# FRONT_MCU_v1.net
KiCad netlist of a schematic drawn in Altium Designer
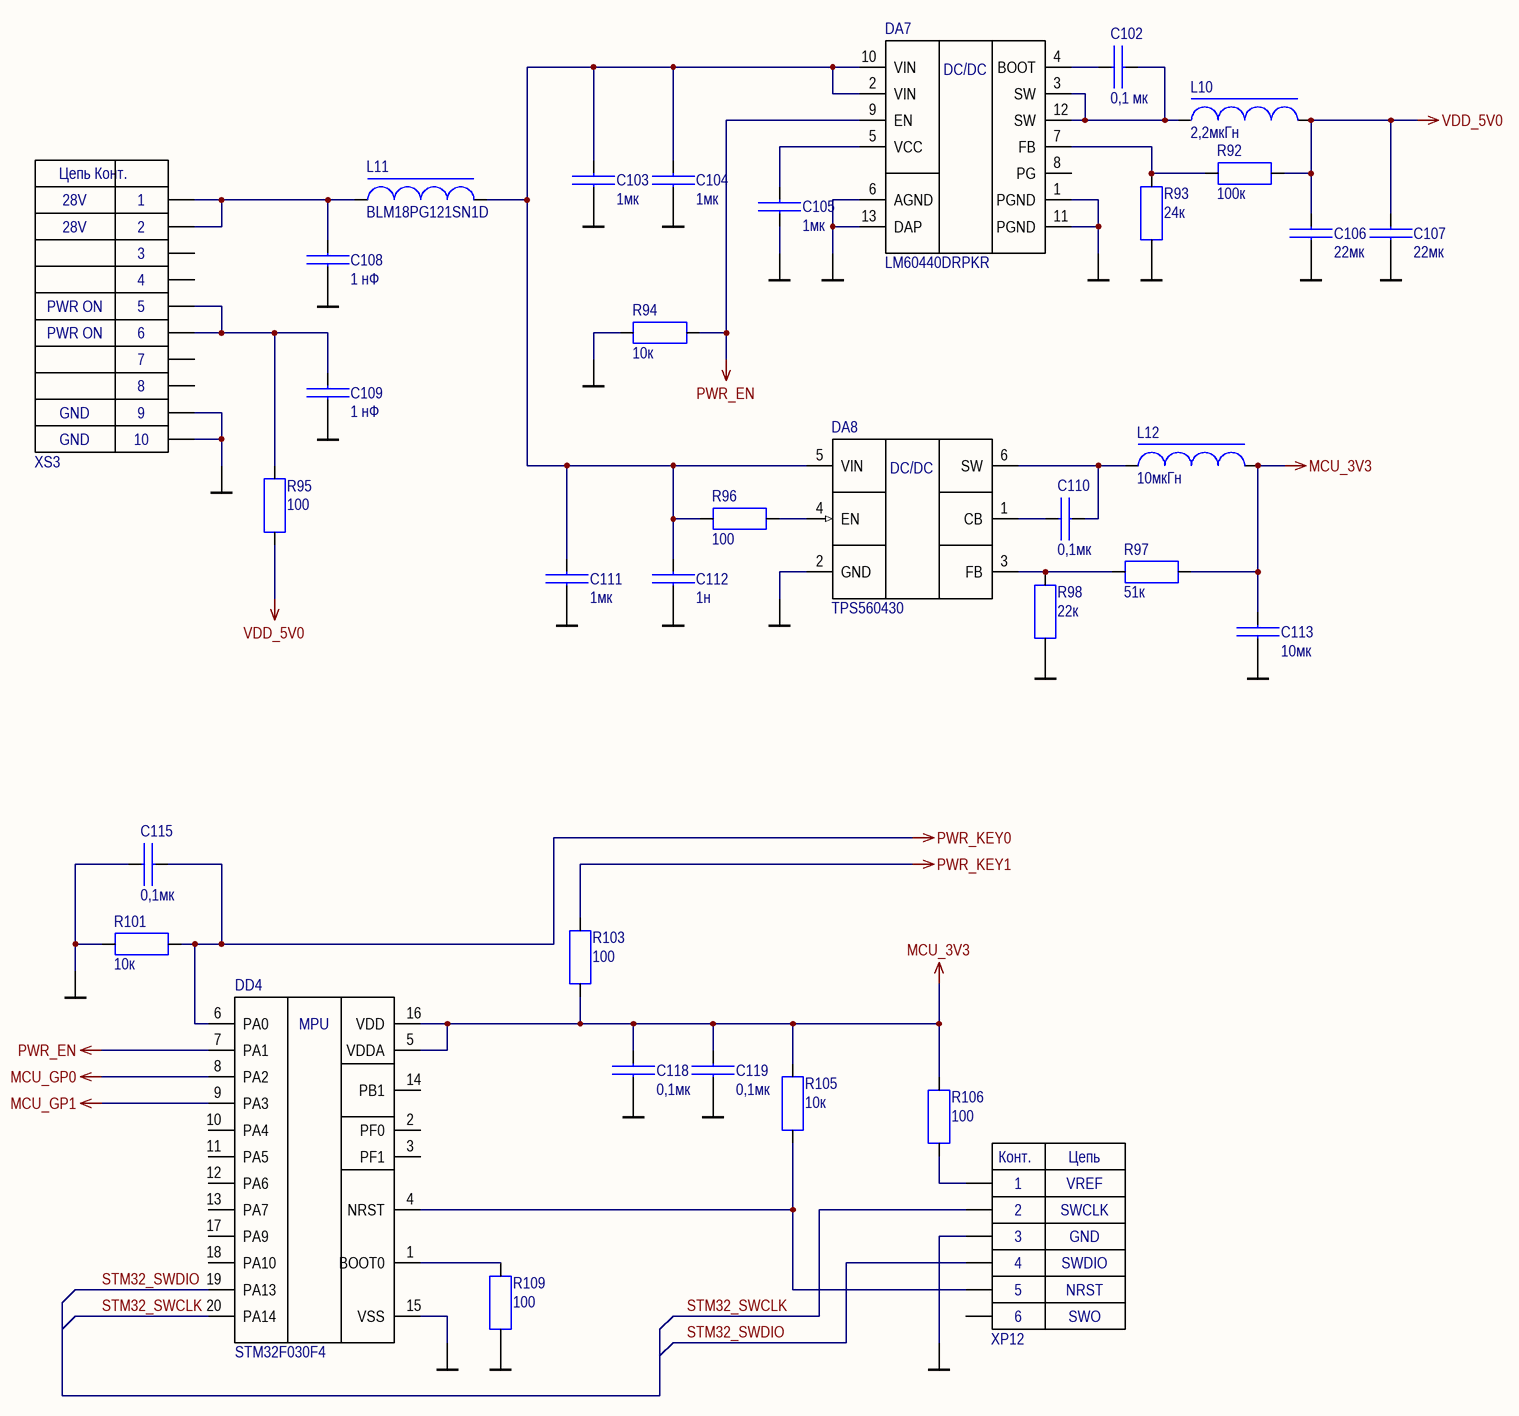
[diagram p0: FRONT_MCU_v1.SchDoc]

(export (version "E")
  (design (tool "Eeschema 10.0.6"))
  (components
    (comp (ref "C102")
      (value "CC0402KRX5R6BB104")
      (footprint "CAPC1005X05L")
      (description "ЧИП конденсатор")
      (fields
        (field (name "NOMINAL") "0,1 мк")
        (field (name "MANUFACTURER") "Yageo")
        (field (name "TOLERANCE") "10%")
      )
      (libsource (lib "Database_Gost") (part "Capacitor const"))
    )
    (comp (ref "C103")
      (value "CC0805KKX7R9BB105")
      (footprint "CAPC2012X09L")
      (description "ЧИП конденсатор")
      (fields
        (field (name "NOMINAL") "1мк")
        (field (name "MANUFACTURER") "Yageo")
        (field (name "TOLERANCE") "0,1")
      )
      (libsource (lib "Database_Gost") (part "Capacitor const"))
    )
    (comp (ref "C104")
      (value "CC0805KKX7R9BB105")
      (footprint "CAPC2012X09L")
      (description "ЧИП конденсатор")
      (fields
        (field (name "NOMINAL") "1мк")
        (field (name "MANUFACTURER") "Yageo")
        (field (name "TOLERANCE") "0,1")
      )
      (libsource (lib "Database_Gost") (part "Capacitor const"))
    )
    (comp (ref "C105")
      (value "CC0402KRX5R5BB105")
      (footprint "CAPC1005X05L")
      (description "ЧИП конденсатор")
      (fields
        (field (name "NOMINAL") "1мк")
        (field (name "MANUFACTURER") "Yageo")
        (field (name "TOLERANCE") "10%")
      )
      (libsource (lib "Database_Gost") (part "Capacitor const"))
    )
    (comp (ref "C106")
      (value "CC0805MKX5R5BB226")
      (footprint "CAPC2012X09L")
      (description "ЧИП конденсатор")
      (fields
        (field (name "NOMINAL") "22мк")
        (field (name "MANUFACTURER") "Yageo")
        (field (name "TOLERANCE") "0,2")
      )
      (libsource (lib "Database_Gost") (part "Capacitor const"))
    )
    (comp (ref "C107")
      (value "CC0805MKX5R5BB226")
      (footprint "CAPC2012X09L")
      (description "ЧИП конденсатор")
      (fields
        (field (name "NOMINAL") "22мк")
        (field (name "MANUFACTURER") "Yageo")
        (field (name "TOLERANCE") "0,2")
      )
      (libsource (lib "Database_Gost") (part "Capacitor const"))
    )
    (comp (ref "C108")
      (value "~")
      (footprint "CAPC1005X05L")
      (description "ЧИП конденсатор")
      (fields
        (field (name "NOMINAL") "1 нФ")
        (field (name "MANUFACTURER") "Yageo")
        (field (name "MANUFACTURERPARTNUMBER") "C0402C102J5GACTU")
      )
      (libsource (lib "Database_Gost") (part "Capacitor const"))
    )
    (comp (ref "C109")
      (value "~")
      (footprint "CAPC1005X05L")
      (description "ЧИП конденсатор")
      (fields
        (field (name "NOMINAL") "1 нФ")
        (field (name "MANUFACTURER") "Yageo")
        (field (name "MANUFACTURERPARTNUMBER") "C0402C102J5GACTU")
      )
      (libsource (lib "Database_Gost") (part "Capacitor const"))
    )
    (comp (ref "C110")
      (value "CC0603KRX7R9BB103")
      (footprint "CAPC1608X08L")
      (description "ЧИП конденсатор")
      (fields
        (field (name "NOMINAL") "0,1мк")
        (field (name "MANUFACTURER") "Yageo")
        (field (name "TOLERANCE") "10%")
      )
      (libsource (lib "Database_Gost") (part "Capacitor const"))
    )
    (comp (ref "C111")
      (value "CC0805KKX7R9BB105")
      (footprint "CAPC2012X09L")
      (description "ЧИП конденсатор")
      (fields
        (field (name "NOMINAL") "1мк")
        (field (name "MANUFACTURER") "Yageo")
        (field (name "TOLERANCE") "0,1")
      )
      (libsource (lib "Database_Gost") (part "Capacitor const"))
    )
    (comp (ref "C112")
      (value "C0402C102J5GACTU")
      (footprint "CAPC1005X05L")
      (description "ЧИП конденсатор")
      (fields
        (field (name "NOMINAL") "1н")
        (field (name "MANUFACTURER") "Yageo")
        (field (name "TOLERANCE") "5%")
      )
      (libsource (lib "Database_Gost") (part "Capacitor const"))
    )
    (comp (ref "C113")
      (value "CC0805KKX5R8BB106")
      (footprint "CAPC2012X09L")
      (description "ЧИП конденсатор")
      (fields
        (field (name "NOMINAL") "10мк")
        (field (name "MANUFACTURER") "Yageo")
        (field (name "TOLERANCE") "0,1")
      )
      (libsource (lib "Database_Gost") (part "Capacitor const"))
    )
    (comp (ref "C115")
      (value "CC0402KRX5R6BB104")
      (footprint "CAPC1005X05L")
      (description "ЧИП конденсатор")
      (fields
        (field (name "NOMINAL") "0,1мк")
        (field (name "MANUFACTURER") "Yageo")
        (field (name "TOLERANCE") "10%")
      )
      (libsource (lib "Database_Gost") (part "Capacitor const"))
    )
    (comp (ref "C118")
      (value "CC0402KRX5R6BB104")
      (footprint "CAPC1005X05L")
      (description "ЧИП конденсатор")
      (fields
        (field (name "NOMINAL") "0,1мк")
        (field (name "MANUFACTURER") "Yageo")
        (field (name "TOLERANCE") "10%")
      )
      (libsource (lib "Database_Gost") (part "Capacitor const"))
    )
    (comp (ref "C119")
      (value "CC0402KRX5R6BB104")
      (footprint "CAPC1005X05L")
      (description "ЧИП конденсатор")
      (fields
        (field (name "NOMINAL") "0,1мк")
        (field (name "MANUFACTURER") "Yageo")
        (field (name "TOLERANCE") "10%")
      )
      (libsource (lib "Database_Gost") (part "Capacitor const"))
    )
    (comp (ref "DA7")
      (value "LM60440DRPKR")
      (footprint "WQFN-13")
      (description "3.8-V to 36-V, 4-A Ultra-Small Synchronous Step-Down Converter")
      (fields (field (name "MANUFACTURER") "TI"))
      (libsource (lib "Chips_single") (part "LM60440DRPKR"))
    )
    (comp (ref "DA8")
      (value "TPS560430")
      (footprint "SOT95P280X145-6L")
      (description "SIMPLE SWITCHER® 4-V to 36-V, 600-mA Synchronous Step-Down Converter")
      (fields (field (name "MANUFACTURER") "TI"))
      (libsource (lib "Chips_single") (part "TPS560430"))
    )
    (comp (ref "DD4")
      (value "STM32F030F4")
      (footprint "TSOP65P640X120-20L")
      (fields (field (name "MANUFACTURER") "STM"))
      (libsource (lib "Chips_single") (part "STM32F030F4"))
    )
    (comp (ref "L10")
      (value "XGL4020-222ME")
      (footprint "INDCXGL4020")
      (description "Shielded Power Inductors")
      (fields (field (name "NOMINAL") "2,2мкГн") (field (name "MANUFACTURER") "Coilcraft"))
      (libsource (lib "Database_Gost") (part "Inductor ferr"))
    )
    (comp (ref "L11")
      (value "BLM18PG121SN1D")
      (footprint "INDC1608X05L")
      (description "Chip Ferrite Beads (0603 Size)")
      (fields (field (name "NOMINAL") "BLM18PG121SN1D") (field (name "MANUFACTURER") "Murata"))
      (libsource (lib "Database_Gost") (part "Inductor ferr"))
    )
    (comp (ref "L12")
      (value "1812PS-103KR")
      (footprint "INDC1812PS")
      (description "Shielded High SRF Inductors")
      (fields (field (name "NOMINAL") "10мкГн") (field (name "MANUFACTURER") "Coilcraft"))
      (libsource (lib "Database_Gost") (part "Inductor ferr"))
    )
    (comp (ref "R92")
      (value "RC0402JR-07100KL")
      (footprint "RESC1005X04L")
      (description "ЧИП резистор")
      (fields
        (field (name "NOMINAL") "100к")
        (field (name "MANUFACTURER") "Yageo")
        (field (name "TOLERANCE") "5%")
      )
      (libsource (lib "Database_Gost") (part "Resistor const"))
    )
    (comp (ref "R93")
      (value "RC0402JR-0724KL")
      (footprint "RESC1005X04L")
      (description "ЧИП резистор")
      (fields
        (field (name "NOMINAL") "24к")
        (field (name "MANUFACTURER") "Yageo")
        (field (name "TOLERANCE") "5%")
      )
      (libsource (lib "Database_Gost") (part "Resistor const"))
    )
    (comp (ref "R94")
      (value "RC0402JR-0710KL")
      (footprint "RESC1005X04L")
      (description "ЧИП резистор")
      (fields
        (field (name "NOMINAL") "10к")
        (field (name "MANUFACTURER") "Yageo")
        (field (name "TOLERANCE") "5%")
      )
      (libsource (lib "Database_Gost") (part "Resistor const"))
    )
    (comp (ref "R95")
      (value "RC0402JR-07100RL")
      (footprint "RESC1005X04L")
      (description "ЧИП резистор")
      (fields
        (field (name "NOMINAL") "100")
        (field (name "MANUFACTURER") "Yageo")
        (field (name "TOLERANCE") "5%")
      )
      (libsource (lib "Database_Gost") (part "Resistor const"))
    )
    (comp (ref "R96")
      (value "RC0402JR-07100RL")
      (footprint "RESC1005X04L")
      (description "ЧИП резистор")
      (fields
        (field (name "NOMINAL") "100")
        (field (name "MANUFACTURER") "Yageo")
        (field (name "TOLERANCE") "5%")
      )
      (libsource (lib "Database_Gost") (part "Resistor const"))
    )
    (comp (ref "R97")
      (value "RC0402JR-0751KL")
      (footprint "RESC1005X04L")
      (description "ЧИП резистор")
      (fields
        (field (name "NOMINAL") "51к")
        (field (name "MANUFACTURER") "Yageo")
        (field (name "TOLERANCE") "5%")
      )
      (libsource (lib "Database_Gost") (part "Resistor const"))
    )
    (comp (ref "R98")
      (value "RC0402JR-0722KL")
      (footprint "RESC1005X04L")
      (description "ЧИП резистор")
      (fields
        (field (name "NOMINAL") "22к")
        (field (name "MANUFACTURER") "Yageo")
        (field (name "TOLERANCE") "5%")
      )
      (libsource (lib "Database_Gost") (part "Resistor const"))
    )
    (comp (ref "R101")
      (value "RC0402JR-0710KL")
      (footprint "RESC1005X04L")
      (description "ЧИП резистор")
      (fields
        (field (name "NOMINAL") "10к")
        (field (name "MANUFACTURER") "Yageo")
        (field (name "TOLERANCE") "5%")
      )
      (libsource (lib "Database_Gost") (part "Resistor const"))
    )
    (comp (ref "R103")
      (value "RC0402JR-07100RL")
      (footprint "RESC1005X04L")
      (description "ЧИП резистор")
      (fields
        (field (name "NOMINAL") "100")
        (field (name "MANUFACTURER") "Yageo")
        (field (name "TOLERANCE") "5%")
      )
      (libsource (lib "Database_Gost") (part "Resistor const"))
    )
    (comp (ref "R105")
      (value "RC0402JR-0710KL")
      (footprint "RESC1005X04L")
      (description "ЧИП резистор")
      (fields
        (field (name "NOMINAL") "10к")
        (field (name "MANUFACTURER") "Yageo")
        (field (name "TOLERANCE") "5%")
      )
      (libsource (lib "Database_Gost") (part "Resistor const"))
    )
    (comp (ref "R106")
      (value "RC0402JR-07100RL")
      (footprint "RESC1005X04L")
      (description "ЧИП резистор")
      (fields
        (field (name "NOMINAL") "100")
        (field (name "MANUFACTURER") "Yageo")
        (field (name "TOLERANCE") "5%")
      )
      (libsource (lib "Database_Gost") (part "Resistor const"))
    )
    (comp (ref "R109")
      (value "RC0402JR-07100RL")
      (footprint "RESC1005X04L")
      (description "ЧИП резистор")
      (fields
        (field (name "NOMINAL") "100")
        (field (name "MANUFACTURER") "Yageo")
        (field (name "TOLERANCE") "5%")
      )
      (libsource (lib "Database_Gost") (part "Resistor const"))
    )
    (comp (ref "XP12")
      (value "PLS-6")
      (footprint "HDR1X6")
      (libsource (lib "Connectors") (part "STM32 S-LINK PLS-6"))
    )
    (comp (ref "XS3")
      (value "FH12-10S-0.5SVA")
      (footprint "FH12-10S-0.5SH")
      (fields (field (name "MANUFACTURER") "Hirose"))
      (libsource (lib "Connectors") (part "FH12-10S-0.5SVA"))
    )
  )
  (nets
    (net (code "1") (name "/STM32_SWCLK") (class "Default")
      (node (ref "DD4") (pin "20") (pinfunction "PA14_20") (pintype "passive"))
      (node (ref "XP12") (pin "2") (pinfunction "2_2") (pintype "passive"))
    )
    (net (code "2") (name "/STM32_SWDIO") (class "Default")
      (node (ref "DD4") (pin "19") (pinfunction "PA13_19") (pintype "passive"))
      (node (ref "XP12") (pin "4") (pinfunction "4_4") (pintype "passive"))
    )
    (net (code "3") (name "GND") (class "Default")
      (node (ref "C103") (pin "1") (pinfunction "1_1") (pintype "passive"))
      (node (ref "C104") (pin "1") (pinfunction "1_1") (pintype "passive"))
      (node (ref "C105") (pin "1") (pinfunction "1_1") (pintype "passive"))
      (node (ref "C106") (pin "1") (pinfunction "1_1") (pintype "passive"))
      (node (ref "C107") (pin "1") (pinfunction "1_1") (pintype "passive"))
      (node (ref "C108") (pin "1") (pinfunction "1_1") (pintype "passive"))
      (node (ref "C109") (pin "1") (pinfunction "1_1") (pintype "passive"))
      (node (ref "C111") (pin "2") (pinfunction "2_2") (pintype "passive"))
      (node (ref "C112") (pin "2") (pinfunction "2_2") (pintype "passive"))
      (node (ref "C113") (pin "1") (pinfunction "1_1") (pintype "passive"))
      (node (ref "C115") (pin "1") (pinfunction "1_1") (pintype "passive"))
      (node (ref "C118") (pin "2") (pinfunction "2_2") (pintype "passive"))
      (node (ref "C119") (pin "2") (pinfunction "2_2") (pintype "passive"))
      (node (ref "DA7") (pin "1") (pinfunction "PGND_1") (pintype "passive"))
      (node (ref "DA7") (pin "11") (pinfunction "PGND_11") (pintype "passive"))
      (node (ref "DA7") (pin "13") (pinfunction "DAP_13") (pintype "passive"))
      (node (ref "DA7") (pin "6") (pinfunction "AGND_6") (pintype "passive"))
      (node (ref "DA8") (pin "2") (pinfunction "GND_2") (pintype "passive"))
      (node (ref "DD4") (pin "15") (pinfunction "VSS_15") (pintype "passive"))
      (node (ref "R101") (pin "2") (pinfunction "2_2") (pintype "passive"))
      (node (ref "R109") (pin "1") (pinfunction "1_1") (pintype "passive"))
      (node (ref "R93") (pin "2") (pinfunction "2_2") (pintype "passive"))
      (node (ref "R94") (pin "2") (pinfunction "2_2") (pintype "passive"))
      (node (ref "R98") (pin "1") (pinfunction "1_1") (pintype "passive"))
      (node (ref "XP12") (pin "3") (pinfunction "3_3") (pintype "passive"))
      (node (ref "XS3") (pin "10") (pinfunction "10_10") (pintype "passive"))
      (node (ref "XS3") (pin "9") (pinfunction "9_9") (pintype "passive"))
    )
    (net (code "4") (name "MCU_3V3") (class "Default")
      (node (ref "C113") (pin "2") (pinfunction "2_2") (pintype "passive"))
      (node (ref "C118") (pin "1") (pinfunction "1_1") (pintype "passive"))
      (node (ref "C119") (pin "1") (pinfunction "1_1") (pintype "passive"))
      (node (ref "DD4") (pin "16") (pinfunction "VDD_16") (pintype "passive"))
      (node (ref "DD4") (pin "5") (pinfunction "VDDA_5") (pintype "passive"))
      (node (ref "L12") (pin "1") (pinfunction "1_1") (pintype "passive"))
      (node (ref "R103") (pin "1") (pinfunction "1_1") (pintype "passive"))
      (node (ref "R105") (pin "2") (pinfunction "2_2") (pintype "passive"))
      (node (ref "R106") (pin "2") (pinfunction "2_2") (pintype "passive"))
      (node (ref "R97") (pin "1") (pinfunction "1_1") (pintype "passive"))
    )
    (net (code "5") (name "MCU_GP0") (class "Default")
      (node (ref "DD4") (pin "8") (pinfunction "PA2_8") (pintype "passive"))
    )
    (net (code "6") (name "MCU_GP1") (class "Default")
      (node (ref "DD4") (pin "9") (pinfunction "PA3_9") (pintype "passive"))
    )
    (net (code "7") (name "Net-(C102-Pad2)") (class "Default")
      (node (ref "C102") (pin "2") (pinfunction "2_2") (pintype "passive"))
      (node (ref "DA7") (pin "12") (pinfunction "SW_12") (pintype "passive"))
      (node (ref "DA7") (pin "3") (pinfunction "SW_3") (pintype "passive"))
      (node (ref "L10") (pin "2") (pinfunction "2_2") (pintype "passive"))
    )
    (net (code "8") (name "Net-(C108-Pad2)") (class "Default")
      (node (ref "C108") (pin "2") (pinfunction "2_2") (pintype "passive"))
      (node (ref "L11") (pin "2") (pinfunction "2_2") (pintype "passive"))
      (node (ref "XS3") (pin "1") (pinfunction "1_1") (pintype "passive"))
      (node (ref "XS3") (pin "2") (pinfunction "2_2") (pintype "passive"))
    )
    (net (code "9") (name "Net-(C109-Pad2)") (class "Default")
      (node (ref "C109") (pin "2") (pinfunction "2_2") (pintype "passive"))
      (node (ref "R95") (pin "2") (pinfunction "2_2") (pintype "passive"))
      (node (ref "XS3") (pin "5") (pinfunction "5_5") (pintype "passive"))
      (node (ref "XS3") (pin "6") (pinfunction "6_6") (pintype "passive"))
    )
    (net (code "10") (name "Net-(DA7-BOOT)") (class "Default")
      (node (ref "C102") (pin "1") (pinfunction "1_1") (pintype "passive"))
      (node (ref "DA7") (pin "4") (pinfunction "BOOT_4") (pintype "passive"))
    )
    (net (code "11") (name "Net-(DA7-FB)") (class "Default")
      (node (ref "DA7") (pin "7") (pinfunction "FB_7") (pintype "passive"))
      (node (ref "R92") (pin "2") (pinfunction "2_2") (pintype "passive"))
      (node (ref "R93") (pin "1") (pinfunction "1_1") (pintype "passive"))
    )
    (net (code "12") (name "Net-(DA7-VCC)") (class "Default")
      (node (ref "C105") (pin "2") (pinfunction "2_2") (pintype "passive"))
      (node (ref "DA7") (pin "5") (pinfunction "VCC_5") (pintype "passive"))
    )
    (net (code "13") (name "Net-(DA8-CB)") (class "Default")
      (node (ref "C110") (pin "1") (pinfunction "1_1") (pintype "passive"))
      (node (ref "DA8") (pin "1") (pinfunction "CB_1") (pintype "passive"))
    )
    (net (code "14") (name "Net-(DA8-EN)") (class "Default")
      (node (ref "DA8") (pin "4") (pinfunction "EN_4") (pintype "input"))
      (node (ref "R96") (pin "2") (pinfunction "2_2") (pintype "passive"))
    )
    (net (code "15") (name "Net-(DA8-FB)") (class "Default")
      (node (ref "DA8") (pin "3") (pinfunction "FB_3") (pintype "passive"))
      (node (ref "R97") (pin "2") (pinfunction "2_2") (pintype "passive"))
      (node (ref "R98") (pin "2") (pinfunction "2_2") (pintype "passive"))
    )
    (net (code "16") (name "Net-(DA8-SW)") (class "Default")
      (node (ref "C110") (pin "2") (pinfunction "2_2") (pintype "passive"))
      (node (ref "DA8") (pin "6") (pinfunction "SW_6") (pintype "passive"))
      (node (ref "L12") (pin "2") (pinfunction "2_2") (pintype "passive"))
    )
    (net (code "17") (name "Net-(DA8-VIN)") (class "Default")
      (node (ref "C103") (pin "2") (pinfunction "2_2") (pintype "passive"))
      (node (ref "C104") (pin "2") (pinfunction "2_2") (pintype "passive"))
      (node (ref "C111") (pin "1") (pinfunction "1_1") (pintype "passive"))
      (node (ref "C112") (pin "1") (pinfunction "1_1") (pintype "passive"))
      (node (ref "DA7") (pin "10") (pinfunction "VIN_10") (pintype "passive"))
      (node (ref "DA7") (pin "2") (pinfunction "VIN_2") (pintype "passive"))
      (node (ref "DA8") (pin "5") (pinfunction "VIN_5") (pintype "passive"))
      (node (ref "L11") (pin "1") (pinfunction "1_1") (pintype "passive"))
      (node (ref "R96") (pin "1") (pinfunction "1_1") (pintype "passive"))
    )
    (net (code "18") (name "Net-(DD4-BOOT0)") (class "Default")
      (node (ref "DD4") (pin "1") (pinfunction "BOOT0_1") (pintype "passive"))
      (node (ref "R109") (pin "2") (pinfunction "2_2") (pintype "passive"))
    )
    (net (code "19") (name "Net-(DD4-NRST)") (class "Default")
      (node (ref "DD4") (pin "4") (pinfunction "NRST_4") (pintype "passive"))
      (node (ref "R105") (pin "1") (pinfunction "1_1") (pintype "passive"))
      (node (ref "XP12") (pin "5") (pinfunction "5_5") (pintype "passive"))
    )
    (net (code "20") (name "Net-(R106-Pad1)") (class "Default")
      (node (ref "R106") (pin "1") (pinfunction "1_1") (pintype "passive"))
      (node (ref "XP12") (pin "1") (pinfunction "1_1") (pintype "passive"))
    )
    (net (code "21") (name "PWR_EN") (class "Default")
      (node (ref "DA7") (pin "9") (pinfunction "EN_9") (pintype "passive"))
      (node (ref "DD4") (pin "7") (pinfunction "PA1_7") (pintype "passive"))
      (node (ref "R94") (pin "1") (pinfunction "1_1") (pintype "passive"))
    )
    (net (code "22") (name "PWR_KEY0") (class "Default")
      (node (ref "C115") (pin "2") (pinfunction "2_2") (pintype "passive"))
      (node (ref "DD4") (pin "6") (pinfunction "PA0_6") (pintype "passive"))
      (node (ref "R101") (pin "1") (pinfunction "1_1") (pintype "passive"))
    )
    (net (code "23") (name "PWR_KEY1") (class "Default")
      (node (ref "R103") (pin "2") (pinfunction "2_2") (pintype "passive"))
    )
    (net (code "24") (name "VDD_5V0") (class "Default")
      (node (ref "C106") (pin "2") (pinfunction "2_2") (pintype "passive"))
      (node (ref "C107") (pin "2") (pinfunction "2_2") (pintype "passive"))
      (node (ref "L10") (pin "1") (pinfunction "1_1") (pintype "passive"))
      (node (ref "R92") (pin "1") (pinfunction "1_1") (pintype "passive"))
      (node (ref "R95") (pin "1") (pinfunction "1_1") (pintype "passive"))
    )
    (net (code "25") (name "unconnected-(DA7-PG-Pad8)") (class "Default")
      (node (ref "DA7") (pin "8") (pinfunction "PG_8") (pintype "passive"))
    )
    (net (code "26") (name "unconnected-(DD4-PA4-Pad10)") (class "Default")
      (node (ref "DD4") (pin "10") (pinfunction "PA4_10") (pintype "passive"))
    )
    (net (code "27") (name "unconnected-(DD4-PA5-Pad11)") (class "Default")
      (node (ref "DD4") (pin "11") (pinfunction "PA5_11") (pintype "passive"))
    )
    (net (code "28") (name "unconnected-(DD4-PA6-Pad12)") (class "Default")
      (node (ref "DD4") (pin "12") (pinfunction "PA6_12") (pintype "passive"))
    )
    (net (code "29") (name "unconnected-(DD4-PA7-Pad13)") (class "Default")
      (node (ref "DD4") (pin "13") (pinfunction "PA7_13") (pintype "passive"))
    )
    (net (code "30") (name "unconnected-(DD4-PA9-Pad17)") (class "Default")
      (node (ref "DD4") (pin "17") (pinfunction "PA9_17") (pintype "passive"))
    )
    (net (code "31") (name "unconnected-(DD4-PA10-Pad18)") (class "Default")
      (node (ref "DD4") (pin "18") (pinfunction "PA10_18") (pintype "passive"))
    )
    (net (code "32") (name "unconnected-(DD4-PB1-Pad14)") (class "Default")
      (node (ref "DD4") (pin "14") (pinfunction "PB1_14") (pintype "passive"))
    )
    (net (code "33") (name "unconnected-(DD4-PF0-Pad2)") (class "Default")
      (node (ref "DD4") (pin "2") (pinfunction "PF0_2") (pintype "passive"))
    )
    (net (code "34") (name "unconnected-(DD4-PF1-Pad3)") (class "Default")
      (node (ref "DD4") (pin "3") (pinfunction "PF1_3") (pintype "passive"))
    )
    (net (code "35") (name "unconnected-(XP12-Pad6)") (class "Default")
      (node (ref "XP12") (pin "6") (pinfunction "6_6") (pintype "passive"))
    )
    (net (code "36") (name "unconnected-(XS3-Pad3)") (class "Default")
      (node (ref "XS3") (pin "3") (pinfunction "3_3") (pintype "passive"))
    )
    (net (code "37") (name "unconnected-(XS3-Pad4)") (class "Default")
      (node (ref "XS3") (pin "4") (pinfunction "4_4") (pintype "passive"))
    )
    (net (code "38") (name "unconnected-(XS3-Pad7)") (class "Default")
      (node (ref "XS3") (pin "7") (pinfunction "7_7") (pintype "passive"))
    )
    (net (code "39") (name "unconnected-(XS3-Pad8)") (class "Default")
      (node (ref "XS3") (pin "8") (pinfunction "8_8") (pintype "passive"))
    )
  )
)
